# SparkFun_tDof-TMF8820.net
KiCad netlist of a schematic drawn in EAGLE
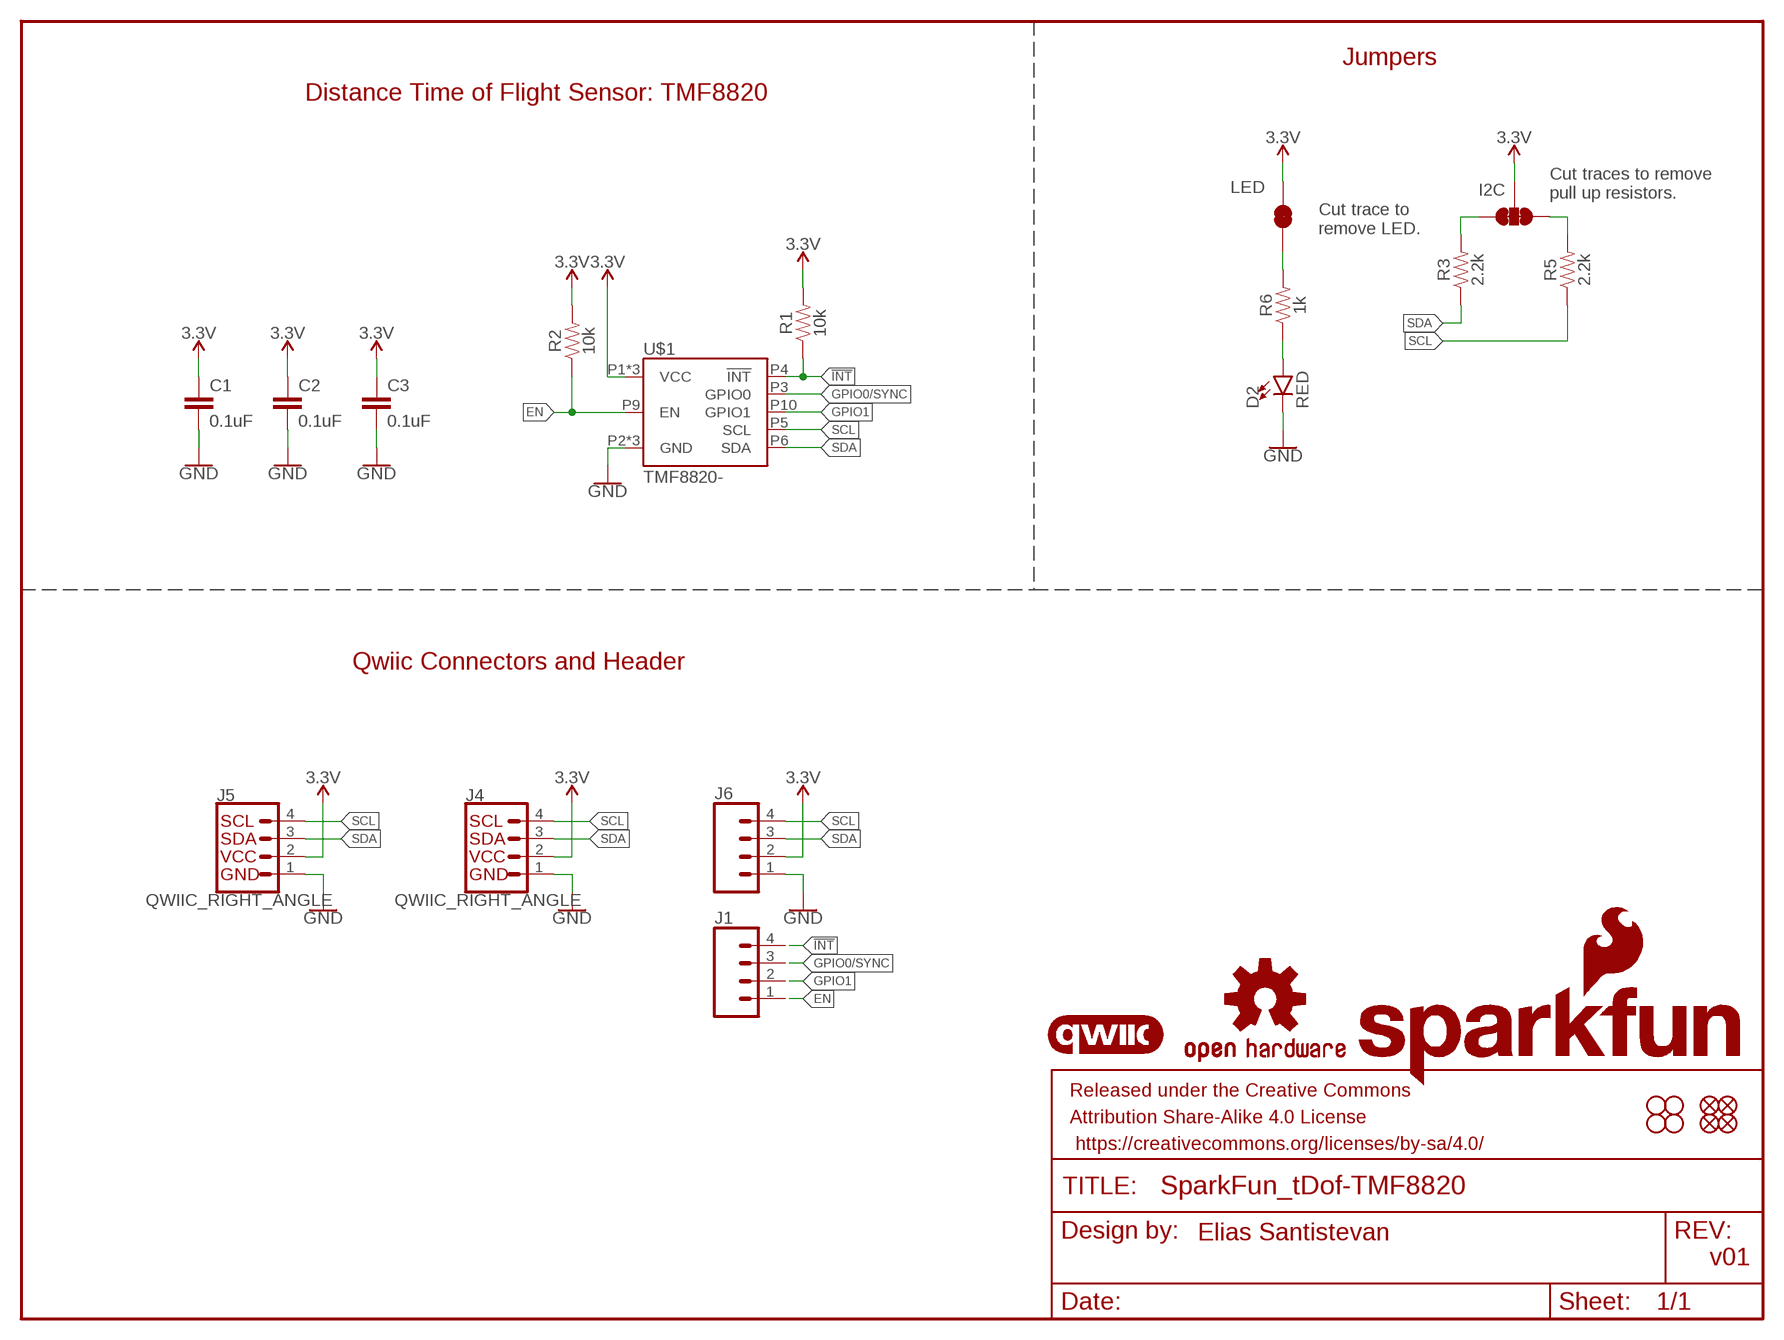
[diagram p0: schematic, sheet 1]

(export (version "E")
  (design (tool "Eeschema 10.0.6"))
  (components
    (comp (ref "C1")
      (value "0.1uF")
      (footprint "eagle-import:0402-TIGHT")
      (libsource (lib "eagle-import") (part "0.1UF-0402T-6.3V-10%-X7R"))
    )
    (comp (ref "C2")
      (value "0.1uF")
      (footprint "eagle-import:0402-TIGHT")
      (libsource (lib "eagle-import") (part "0.1UF-0402T-6.3V-10%-X7R"))
    )
    (comp (ref "C3")
      (value "0.1uF")
      (footprint "eagle-import:0402-TIGHT")
      (libsource (lib "eagle-import") (part "0.1UF-0402T-6.3V-10%-X7R"))
    )
    (comp (ref "D2")
      (value "RED")
      (footprint "eagle-import:LED-0603")
      (libsource (lib "eagle-import") (part "LED-RED0603"))
    )
    (comp (ref "FD5")
      (value "FIDUCIALUFIDUCIAL")
      (footprint "eagle-import:FIDUCIAL-MICRO")
      (libsource (lib "eagle-import") (part "FIDUCIALUFIDUCIAL"))
    )
    (comp (ref "FD6")
      (value "FIDUCIALUFIDUCIAL")
      (footprint "eagle-import:FIDUCIAL-MICRO")
      (libsource (lib "eagle-import") (part "FIDUCIALUFIDUCIAL"))
    )
    (comp (ref "FD7")
      (value "FIDUCIALUFIDUCIAL")
      (footprint "eagle-import:FIDUCIAL-MICRO")
      (libsource (lib "eagle-import") (part "FIDUCIALUFIDUCIAL"))
    )
    (comp (ref "FD8")
      (value "FIDUCIALUFIDUCIAL")
      (footprint "eagle-import:FIDUCIAL-MICRO")
      (libsource (lib "eagle-import") (part "FIDUCIALUFIDUCIAL"))
    )
    (comp (ref "FRAME2")
      (value "FRAME-LETTER")
      (footprint "eagle-import:CREATIVE_COMMONS")
      (libsource (lib "eagle-import") (part "FRAME-LETTER"))
    )
    (comp (ref "H5")
      (value "STAND-OFFTIGHT")
      (footprint "eagle-import:STAND-OFF-TIGHT")
      (libsource (lib "eagle-import") (part "STAND-OFFTIGHT"))
    )
    (comp (ref "H6")
      (value "STAND-OFFTIGHT")
      (footprint "eagle-import:STAND-OFF-TIGHT")
      (libsource (lib "eagle-import") (part "STAND-OFFTIGHT"))
    )
    (comp (ref "H7")
      (value "STAND-OFFTIGHT")
      (footprint "eagle-import:STAND-OFF-TIGHT")
      (libsource (lib "eagle-import") (part "STAND-OFFTIGHT"))
    )
    (comp (ref "H8")
      (value "STAND-OFFTIGHT")
      (footprint "eagle-import:STAND-OFF-TIGHT")
      (libsource (lib "eagle-import") (part "STAND-OFFTIGHT"))
    )
    (comp (ref "I2C")
      (value "I2C_PU")
      (footprint "eagle-import:SMT-JUMPER_3_2-NC_TRACE_SILK")
      (libsource (lib "eagle-import") (part "JUMPER-SMT_3_2-NC_TRACE_SILK"))
    )
    (comp (ref "J1")
      (value "CONN_041X04_NO_SILK_NO_POP")
      (footprint "eagle-import:1X04_NO_SILK")
      (libsource (lib "eagle-import") (part "CONN_041X04_NO_SILK_NO_POP"))
    )
    (comp (ref "J4")
      (value "QWIIC_RIGHT_ANGLE")
      (footprint "eagle-import:JST04_1MM_RA")
      (libsource (lib "eagle-import") (part "QWIIC_CONNECTORJS-1MM"))
    )
    (comp (ref "J5")
      (value "QWIIC_RIGHT_ANGLE")
      (footprint "eagle-import:JST04_1MM_RA")
      (libsource (lib "eagle-import") (part "QWIIC_CONNECTORJS-1MM"))
    )
    (comp (ref "J6")
      (value "CONN_041X04_NO_SILK")
      (footprint "eagle-import:1X04_NO_SILK")
      (libsource (lib "eagle-import") (part "CONN_041X04_NO_SILK"))
    )
    (comp (ref "LED")
      (value "LED")
      (footprint "eagle-import:SMT-JUMPER_2_NC_TRACE_SILK")
      (libsource (lib "eagle-import") (part "JUMPER-SMT_2_NC_TRACE_SILK"))
    )
    (comp (ref "LOGO3")
      (value "SFE_LOGO_NAME_FLAME.1_INCH")
      (footprint "eagle-import:SFE_LOGO_NAME_FLAME_.1")
      (libsource (lib "eagle-import") (part "SFE_LOGO_NAME_FLAME.1_INCH"))
    )
    (comp (ref "LOGO4")
      (value "OSHW-LOGOS")
      (footprint "eagle-import:OSHW-LOGO-S")
      (libsource (lib "eagle-import") (part "OSHW-LOGOS"))
    )
    (comp (ref "R1")
      (value "10k")
      (footprint "eagle-import:0603")
      (libsource (lib "eagle-import") (part "10KOHM-0603-1/10W-1%"))
    )
    (comp (ref "R2")
      (value "10k")
      (footprint "eagle-import:0603")
      (libsource (lib "eagle-import") (part "10KOHM-0603-1/10W-1%"))
    )
    (comp (ref "R3")
      (value "2.2k")
      (footprint "eagle-import:0603")
      (libsource (lib "eagle-import") (part "2.2KOHM-0603-1/10W-1%"))
    )
    (comp (ref "R5")
      (value "2.2k")
      (footprint "eagle-import:0603")
      (libsource (lib "eagle-import") (part "2.2KOHM-0603-1/10W-1%"))
    )
    (comp (ref "R6")
      (value "1k")
      (footprint "eagle-import:0603")
      (libsource (lib "eagle-import") (part "1KOHM-0603-1/10W-1%"))
    )
    (comp (ref "U$1")
      (value "TMF8820-")
      (footprint "eagle-import:TMF882X")
      (libsource (lib "eagle-import") (part "TMF8820-"))
    )
    (comp (ref "U$6")
      (value "QWIIC_LOGO_5MM")
      (footprint "eagle-import:QWIIC_5MM")
      (libsource (lib "eagle-import") (part "QWIIC_LOGO_5MM"))
    )
  )
  (nets
    (net (code "1") (name "/~{INT}") (class "Default")
      (node (ref "J1") (pin "4") (pinfunction "4_4") (pintype "passive"))
      (node (ref "R1") (pin "1") (pinfunction "1_1") (pintype "passive"))
      (node (ref "U$1") (pin "P4") (pinfunction "~{INT}_P4") (pintype "bidirectional"))
    )
    (net (code "2") (name "3.3V") (class "Default")
      (node (ref "C1") (pin "1") (pinfunction "1_1") (pintype "passive"))
      (node (ref "C2") (pin "1") (pinfunction "1_1") (pintype "passive"))
      (node (ref "C3") (pin "1") (pinfunction "1_1") (pintype "passive"))
      (node (ref "I2C") (pin "2") (pinfunction "2_2") (pintype "passive"))
      (node (ref "J4") (pin "2") (pinfunction "2_2") (pintype "power_in"))
      (node (ref "J5") (pin "2") (pinfunction "2_2") (pintype "power_in"))
      (node (ref "J6") (pin "2") (pinfunction "2_2") (pintype "passive"))
      (node (ref "LED") (pin "2") (pinfunction "2_2") (pintype "passive"))
      (node (ref "R1") (pin "2") (pinfunction "2_2") (pintype "passive"))
      (node (ref "R2") (pin "2") (pinfunction "2_2") (pintype "passive"))
      (node (ref "U$1") (pin "P1") (pinfunction "VCC_P1") (pintype "power_in"))
      (node (ref "U$1") (pin "P12") (pinfunction "VCC_P12") (pintype "power_in"))
      (node (ref "U$1") (pin "P7") (pinfunction "VCC_P7") (pintype "power_in"))
    )
    (net (code "3") (name "EN") (class "Default")
      (node (ref "J1") (pin "1") (pinfunction "1_1") (pintype "passive"))
      (node (ref "R2") (pin "1") (pinfunction "1_1") (pintype "passive"))
      (node (ref "U$1") (pin "P9") (pinfunction "EN_P9") (pintype "input"))
    )
    (net (code "4") (name "GND") (class "Default")
      (node (ref "C1") (pin "2") (pinfunction "2_2") (pintype "passive"))
      (node (ref "C2") (pin "2") (pinfunction "2_2") (pintype "passive"))
      (node (ref "C3") (pin "2") (pinfunction "2_2") (pintype "passive"))
      (node (ref "D2") (pin "C") (pinfunction "C_C") (pintype "passive"))
      (node (ref "J4") (pin "1") (pinfunction "1_1") (pintype "power_in"))
      (node (ref "J5") (pin "1") (pinfunction "1_1") (pintype "power_in"))
      (node (ref "J6") (pin "1") (pinfunction "1_1") (pintype "passive"))
      (node (ref "U$1") (pin "P11") (pinfunction "GND_P11") (pintype "power_in"))
      (node (ref "U$1") (pin "P2") (pinfunction "GND_P2") (pintype "power_in"))
      (node (ref "U$1") (pin "P8") (pinfunction "GND_P8") (pintype "power_in"))
    )
    (net (code "5") (name "GPIO0{slash}SYNC") (class "Default")
      (node (ref "J1") (pin "3") (pinfunction "3_3") (pintype "passive"))
      (node (ref "U$1") (pin "P3") (pinfunction "GPIO0_P3") (pintype "bidirectional"))
    )
    (net (code "6") (name "GPIO1") (class "Default")
      (node (ref "J1") (pin "2") (pinfunction "2_2") (pintype "passive"))
      (node (ref "U$1") (pin "P10") (pinfunction "GPIO1_P10") (pintype "bidirectional"))
    )
    (net (code "7") (name "Net-(D2-PadA)") (class "Default")
      (node (ref "D2") (pin "A") (pinfunction "A_A") (pintype "passive"))
      (node (ref "R6") (pin "1") (pinfunction "1_1") (pintype "passive"))
    )
    (net (code "8") (name "Net-(I2C-Pad1)") (class "Default")
      (node (ref "I2C") (pin "1") (pinfunction "1_1") (pintype "passive"))
      (node (ref "R5") (pin "2") (pinfunction "2_2") (pintype "passive"))
    )
    (net (code "9") (name "Net-(I2C-Pad3)") (class "Default")
      (node (ref "I2C") (pin "3") (pinfunction "3_3") (pintype "passive"))
      (node (ref "R3") (pin "2") (pinfunction "2_2") (pintype "passive"))
    )
    (net (code "10") (name "Net-(LED-Pad1)") (class "Default")
      (node (ref "LED") (pin "1") (pinfunction "1_1") (pintype "passive"))
      (node (ref "R6") (pin "2") (pinfunction "2_2") (pintype "passive"))
    )
    (net (code "11") (name "SCL") (class "Default")
      (node (ref "J4") (pin "4") (pinfunction "4_4") (pintype "passive"))
      (node (ref "J5") (pin "4") (pinfunction "4_4") (pintype "passive"))
      (node (ref "J6") (pin "4") (pinfunction "4_4") (pintype "passive"))
      (node (ref "R5") (pin "1") (pinfunction "1_1") (pintype "passive"))
      (node (ref "U$1") (pin "P5") (pinfunction "SCL_P5") (pintype "bidirectional"))
    )
    (net (code "12") (name "SDA") (class "Default")
      (node (ref "J4") (pin "3") (pinfunction "3_3") (pintype "passive"))
      (node (ref "J5") (pin "3") (pinfunction "3_3") (pintype "passive"))
      (node (ref "J6") (pin "3") (pinfunction "3_3") (pintype "passive"))
      (node (ref "R3") (pin "1") (pinfunction "1_1") (pintype "passive"))
      (node (ref "U$1") (pin "P6") (pinfunction "SDA_P6") (pintype "bidirectional"))
    )
  )
)
